# photoresistance_measure.net
KiCad netlist of a schematic drawn in Altium Designer
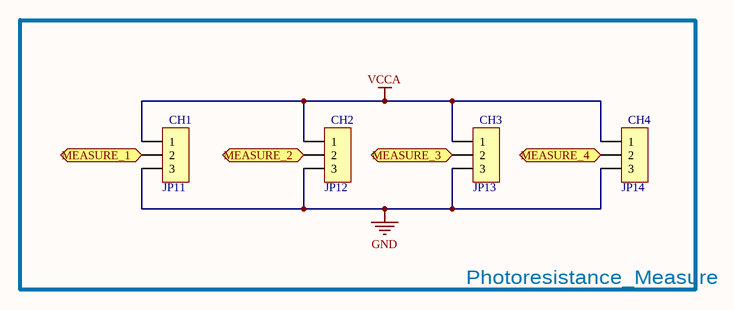
[diagram p0: photoresistance_measure.SchDoc]

(export (version "E")
  (design (tool "Eeschema 10.0.6"))
  (components
    (comp (ref "JP11")
      (value "CH1")
      (footprint "HDR2.54-LI-3P")
      (description "3P接插件")
      (fields (field (name "版权归属") "源创客"))
      (libsource (lib "4.5   - 接插件-脚距2.54") (part "Header 3"))
    )
    (comp (ref "JP12")
      (value "CH2")
      (footprint "HDR2.54-LI-3P")
      (description "3P接插件")
      (fields (field (name "版权归属") "源创客"))
      (libsource (lib "4.5   - 接插件-脚距2.54") (part "Header 3"))
    )
    (comp (ref "JP13")
      (value "CH3")
      (footprint "HDR2.54-LI-3P")
      (description "3P接插件")
      (fields (field (name "版权归属") "源创客"))
      (libsource (lib "4.5   - 接插件-脚距2.54") (part "Header 3"))
    )
    (comp (ref "JP14")
      (value "CH4")
      (footprint "HDR2.54-LI-3P")
      (description "3P接插件")
      (fields (field (name "版权归属") "源创客"))
      (libsource (lib "4.5   - 接插件-脚距2.54") (part "Header 3"))
    )
  )
  (nets
    (net (code "1") (name "/MEASURE_1") (class "Default")
      (node (ref "JP11") (pin "2") (pinfunction "2_2") (pintype "passive"))
    )
    (net (code "2") (name "/MEASURE_2") (class "Default")
      (node (ref "JP12") (pin "2") (pinfunction "2_2") (pintype "passive"))
    )
    (net (code "3") (name "/MEASURE_3") (class "Default")
      (node (ref "JP13") (pin "2") (pinfunction "2_2") (pintype "passive"))
    )
    (net (code "4") (name "/MEASURE_4") (class "Default")
      (node (ref "JP14") (pin "2") (pinfunction "2_2") (pintype "passive"))
    )
    (net (code "5") (name "GND") (class "Default")
      (node (ref "JP11") (pin "3") (pinfunction "3_3") (pintype "passive"))
      (node (ref "JP12") (pin "3") (pinfunction "3_3") (pintype "passive"))
      (node (ref "JP13") (pin "3") (pinfunction "3_3") (pintype "passive"))
      (node (ref "JP14") (pin "3") (pinfunction "3_3") (pintype "passive"))
    )
    (net (code "6") (name "VCCA") (class "Default")
      (node (ref "JP11") (pin "1") (pinfunction "1_1") (pintype "passive"))
      (node (ref "JP12") (pin "1") (pinfunction "1_1") (pintype "passive"))
      (node (ref "JP13") (pin "1") (pinfunction "1_1") (pintype "passive"))
      (node (ref "JP14") (pin "1") (pinfunction "1_1") (pintype "passive"))
    )
  )
)
